# tag_key-v1.net
KiCad netlist of a schematic drawn in EAGLE
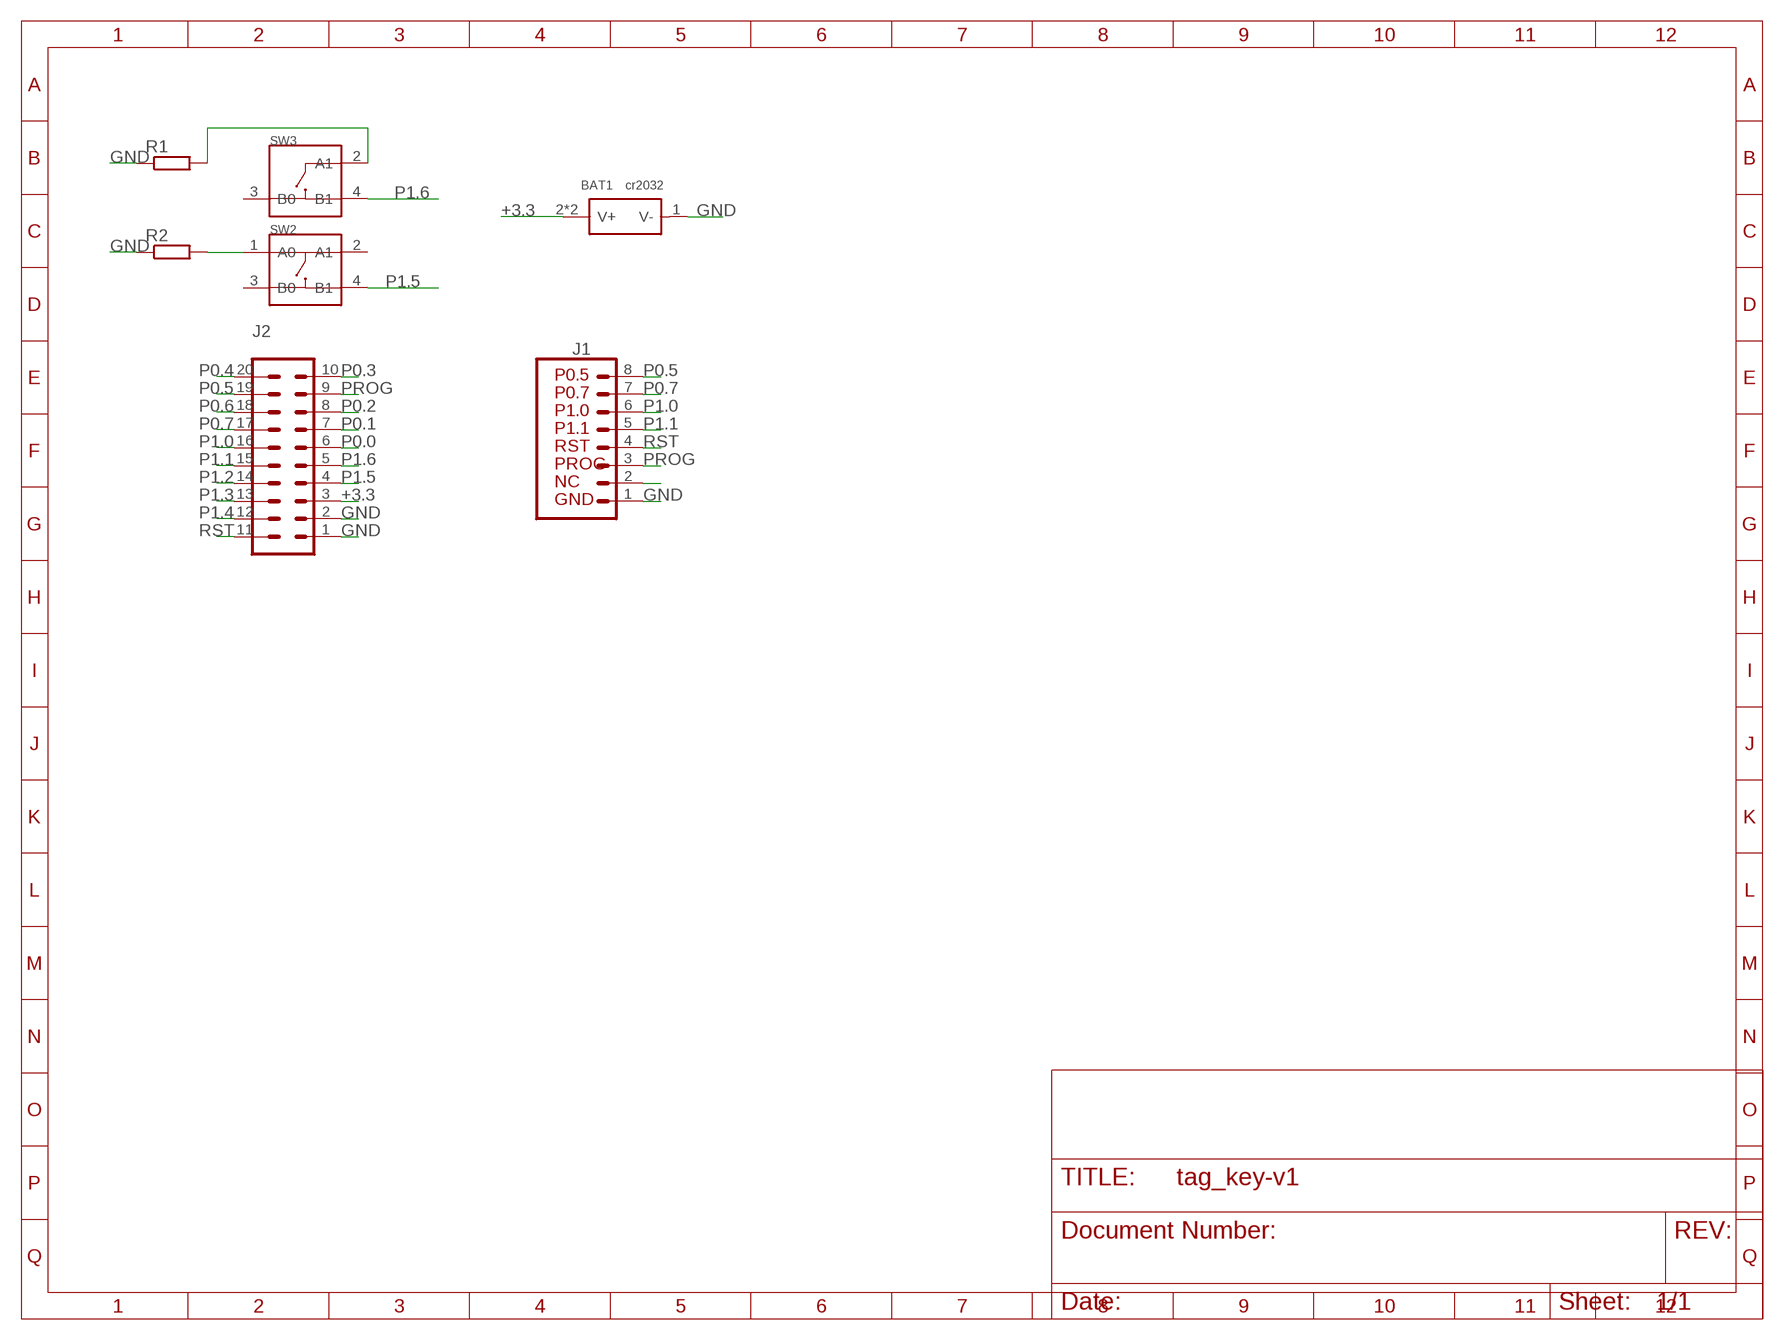
[diagram p0: schematic, sheet 1]

(export (version "E")
  (design (tool "Eeschema 10.0.6"))
  (components
    (comp (ref "BAT1")
      (value "cr2032")
      (footprint "eagle-import:SEEED-OPL-CONNECTOR_BAT2P-20.32-CR2032")
      (libsource (lib "eagle-import") (part "SEEED-OPL-CONNECTOR_DIP-BATTERY-CELL-HOLDER(2032)"))
    )
    (comp (ref "J1")
      (value "SPARKFUN-CONNECTORS_CONN_08\"")
      (footprint "eagle-import:SPARKFUN-CONNECTORS_1X08")
      (libsource (lib "eagle-import") (part "SPARKFUN-CONNECTORS_CONN_08{dblquote}"))
    )
    (comp (ref "J2")
      (value "SPARKFUN-CONNECTORS_CONN_11_1.27MM")
      (footprint "eagle-import:SPARKFUN-CONNECTORS_1X11-1.27MM")
      (libsource (lib "eagle-import") (part "SPARKFUN-CONNECTORS_CONN_11_1.27MM"))
    )
    (comp (ref "R1")
      (value "RESISTOR_R-EU_M0805")
      (footprint "eagle-import:RESISTOR_M0805")
      (libsource (lib "eagle-import") (part "RESISTOR_R-EU_M0805"))
    )
    (comp (ref "R2")
      (value "RESISTOR_R-EU_M0805")
      (footprint "eagle-import:RESISTOR_M0805")
      (libsource (lib "eagle-import") (part "RESISTOR_R-EU_M0805"))
    )
    (comp (ref "SW2")
      (value "SEEED-OPL-SWITCH_SMD-BUTTON(4P-6.0X6.0X7.5MM)")
      (footprint "eagle-import:SEEED-OPL-SWITCH_SW4-SMD-4.5-6.0X6.0X7.5MM")
      (libsource (lib "eagle-import") (part "SEEED-OPL-SWITCH_SMD-BUTTON(4P-6.0X6.0X7.5MM)"))
    )
    (comp (ref "SW3")
      (value "SEEED-OPL-SWITCH_SMD-BUTTON(4P-6.0X6.0X3LEGM)")
      (footprint "eagle-import:SEEED-OPL-SWITCH_SW4-SMD-4.5-6.0X6.0_3LEG")
      (libsource (lib "eagle-import") (part "SEEED-OPL-SWITCH_SMD-BUTTON(4P-6.0X6.0X3LEGM)"))
    )
  )
  (nets
    (net (code "1") (name "/+3.3") (class "Default")
      (node (ref "BAT1") (pin "2") (pinfunction "V+_2") (pintype "bidirectional"))
      (node (ref "BAT1") (pin "3") (pinfunction "V+_3") (pintype "bidirectional"))
      (node (ref "J2") (pin "3") (pinfunction "3_3") (pintype "passive"))
    )
    (net (code "2") (name "/GND") (class "Default")
      (node (ref "BAT1") (pin "1") (pinfunction "V-_1") (pintype "bidirectional"))
      (node (ref "J1") (pin "1") (pinfunction "1_1") (pintype "passive"))
      (node (ref "J2") (pin "1") (pinfunction "1_1") (pintype "passive"))
      (node (ref "J2") (pin "2") (pinfunction "2_2") (pintype "passive"))
      (node (ref "R1") (pin "1") (pinfunction "1_1") (pintype "passive"))
      (node (ref "R2") (pin "1") (pinfunction "1_1") (pintype "passive"))
    )
    (net (code "3") (name "/P0.0") (class "Default")
      (node (ref "J2") (pin "6") (pinfunction "6_6") (pintype "passive"))
    )
    (net (code "4") (name "/P0.1") (class "Default")
      (node (ref "J2") (pin "7") (pinfunction "7_7") (pintype "passive"))
    )
    (net (code "5") (name "/P0.2") (class "Default")
      (node (ref "J2") (pin "8") (pinfunction "8_8") (pintype "passive"))
    )
    (net (code "6") (name "/P0.3") (class "Default")
      (node (ref "J2") (pin "10") (pinfunction "10_10") (pintype "passive"))
    )
    (net (code "7") (name "/P0.4") (class "Default")
      (node (ref "J2") (pin "20") (pinfunction "11_20") (pintype "passive"))
    )
    (net (code "8") (name "/P0.5") (class "Default")
      (node (ref "J1") (pin "8") (pinfunction "8_8") (pintype "passive"))
      (node (ref "J2") (pin "19") (pinfunction "12_19") (pintype "passive"))
    )
    (net (code "9") (name "/P0.6") (class "Default")
      (node (ref "J2") (pin "18") (pinfunction "13_18") (pintype "passive"))
    )
    (net (code "10") (name "/P0.7") (class "Default")
      (node (ref "J1") (pin "7") (pinfunction "7_7") (pintype "passive"))
      (node (ref "J2") (pin "17") (pinfunction "14_17") (pintype "passive"))
    )
    (net (code "11") (name "/P1.0") (class "Default")
      (node (ref "J1") (pin "6") (pinfunction "6_6") (pintype "passive"))
      (node (ref "J2") (pin "16") (pinfunction "15_16") (pintype "passive"))
    )
    (net (code "12") (name "/P1.1") (class "Default")
      (node (ref "J1") (pin "5") (pinfunction "5_5") (pintype "passive"))
      (node (ref "J2") (pin "15") (pinfunction "16_15") (pintype "passive"))
    )
    (net (code "13") (name "/P1.2") (class "Default")
      (node (ref "J2") (pin "14") (pinfunction "17_14") (pintype "passive"))
    )
    (net (code "14") (name "/P1.3") (class "Default")
      (node (ref "J2") (pin "13") (pinfunction "18_13") (pintype "passive"))
    )
    (net (code "15") (name "/P1.4") (class "Default")
      (node (ref "J2") (pin "12") (pinfunction "19_12") (pintype "passive"))
    )
    (net (code "16") (name "/P1.5") (class "Default")
      (node (ref "J2") (pin "4") (pinfunction "4_4") (pintype "passive"))
      (node (ref "SW2") (pin "4") (pinfunction "B1_4") (pintype "bidirectional"))
    )
    (net (code "17") (name "/P1.6") (class "Default")
      (node (ref "J2") (pin "5") (pinfunction "5_5") (pintype "passive"))
      (node (ref "SW3") (pin "4") (pinfunction "B1_4") (pintype "bidirectional"))
    )
    (net (code "18") (name "/PROG") (class "Default")
      (node (ref "J1") (pin "3") (pinfunction "3_3") (pintype "passive"))
      (node (ref "J2") (pin "9") (pinfunction "9_9") (pintype "passive"))
    )
    (net (code "19") (name "/RST") (class "Default")
      (node (ref "J1") (pin "4") (pinfunction "4_4") (pintype "passive"))
      (node (ref "J2") (pin "11") (pinfunction "20_11") (pintype "passive"))
    )
    (net (code "20") (name "Net-(SW2-A0)") (class "Default")
      (node (ref "R2") (pin "2") (pinfunction "2_2") (pintype "passive"))
      (node (ref "SW2") (pin "1") (pinfunction "A0_1") (pintype "bidirectional"))
    )
    (net (code "21") (name "Net-(SW3-A1)") (class "Default")
      (node (ref "R1") (pin "2") (pinfunction "2_2") (pintype "passive"))
      (node (ref "SW3") (pin "2") (pinfunction "A1_2") (pintype "bidirectional"))
    )
    (net (code "22") (name "unconnected-(J1-Pad2)") (class "Default")
      (node (ref "J1") (pin "2") (pinfunction "2_2") (pintype "passive"))
    )
    (net (code "23") (name "unconnected-(SW2-A1-Pad2)") (class "Default")
      (node (ref "SW2") (pin "2") (pinfunction "A1_2") (pintype "bidirectional"))
    )
    (net (code "24") (name "unconnected-(SW2-B0-Pad3)") (class "Default")
      (node (ref "SW2") (pin "3") (pinfunction "B0_3") (pintype "bidirectional"))
    )
    (net (code "25") (name "unconnected-(SW3-B0-Pad3)") (class "Default")
      (node (ref "SW3") (pin "3") (pinfunction "B0_3") (pintype "bidirectional"))
    )
  )
)
